# clock.net
KiCad netlist of a schematic drawn in EAGLE
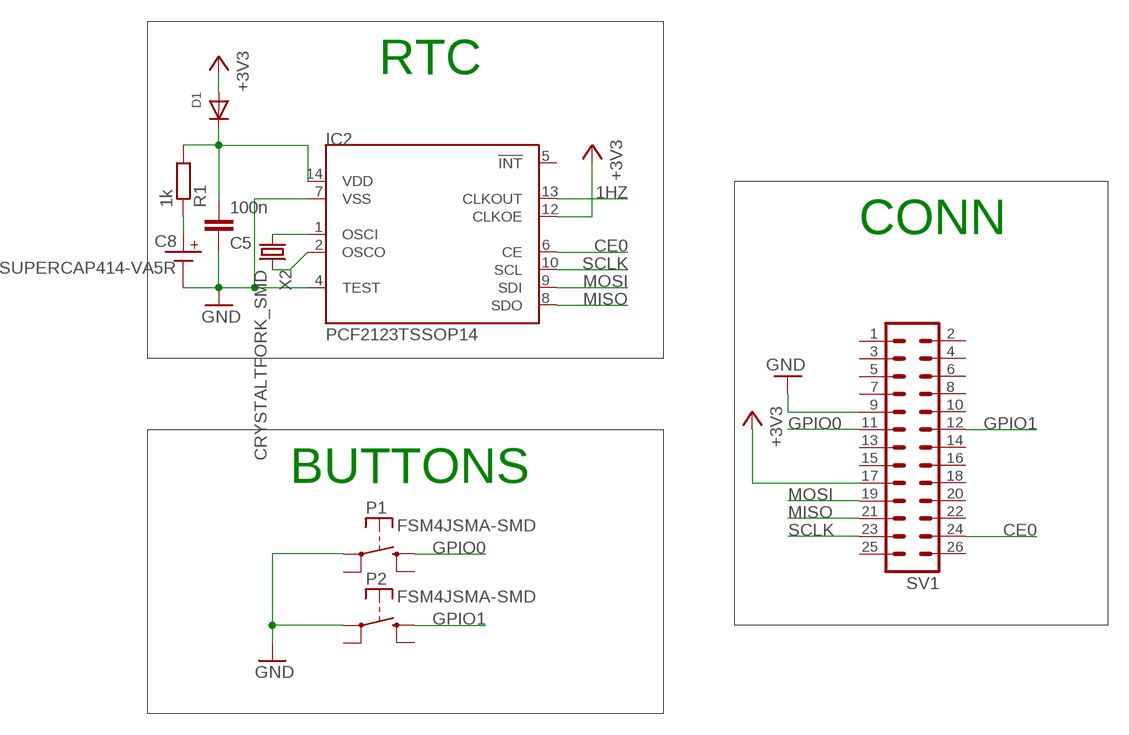
[diagram p0: schematic, sheet 1]

(export (version "E")
  (design (tool "Eeschema 10.0.6"))
  (components
    (comp (ref "C5")
      (value "100n")
      (footprint "eagle-import:C0603K")
      (libsource (lib "eagle-import") (part "C-EUC0603K"))
    )
    (comp (ref "C8")
      (value "SUPERCAP414-VA5R")
      (footprint "eagle-import:414-VA5R")
      (libsource (lib "eagle-import") (part "SUPERCAP414-VA5R"))
    )
    (comp (ref "D1")
      (value "DIODESOD-523")
      (footprint "eagle-import:SOD-523")
      (libsource (lib "eagle-import") (part "DIODESOD-523"))
    )
    (comp (ref "IC2")
      (value "PCF2123TSSOP14")
      (footprint "eagle-import:TSSOP14")
      (libsource (lib "eagle-import") (part "PCF2123TSSOP14"))
    )
    (comp (ref "P1")
      (value "FSM4JSMA-SMD")
      (footprint "eagle-import:FSM4JSMA-SMD")
      (libsource (lib "eagle-import") (part "FSM4JSMA-SMD"))
    )
    (comp (ref "P2")
      (value "FSM4JSMA-SMD")
      (footprint "eagle-import:FSM4JSMA-SMD")
      (libsource (lib "eagle-import") (part "FSM4JSMA-SMD"))
    )
    (comp (ref "R1")
      (value "1k")
      (footprint "eagle-import:R0603")
      (libsource (lib "eagle-import") (part "R-EU_R0603"))
    )
    (comp (ref "SV1")
      (value "MA13-2")
      (footprint "eagle-import:MA13-2")
      (libsource (lib "eagle-import") (part "MA13-2"))
    )
    (comp (ref "X2")
      (value "CRYSTALTFORK_SMD")
      (footprint "eagle-import:TFORK_SMD")
      (libsource (lib "eagle-import") (part "CRYSTALTFORK_SMD"))
    )
  )
  (nets
    (net (code "1") (name "+3V3") (class "Default")
      (node (ref "D1") (pin "A") (pinfunction "A_A") (pintype "passive"))
      (node (ref "IC2") (pin "12") (pinfunction "CLKOE_12") (pintype "input"))
      (node (ref "SV1") (pin "17") (pinfunction "17_17") (pintype "passive"))
    )
    (net (code "2") (name "/1HZ") (class "Default")
      (node (ref "IC2") (pin "13") (pinfunction "CLKOUT_13") (pintype "output"))
    )
    (net (code "3") (name "/CE0") (class "Default")
      (node (ref "IC2") (pin "6") (pinfunction "CE_6") (pintype "input"))
      (node (ref "SV1") (pin "24") (pinfunction "24_24") (pintype "passive"))
    )
    (net (code "4") (name "/GPIO0") (class "Default")
      (node (ref "P1") (pin "P$3") (pinfunction "S_P$3") (pintype "passive"))
      (node (ref "SV1") (pin "11") (pinfunction "11_11") (pintype "passive"))
    )
    (net (code "5") (name "/GPIO1") (class "Default")
      (node (ref "P2") (pin "P$3") (pinfunction "S_P$3") (pintype "passive"))
      (node (ref "SV1") (pin "12") (pinfunction "12_12") (pintype "passive"))
    )
    (net (code "6") (name "/MISO") (class "Default")
      (node (ref "IC2") (pin "8") (pinfunction "SDO_8") (pintype "output"))
      (node (ref "SV1") (pin "21") (pinfunction "21_21") (pintype "passive"))
    )
    (net (code "7") (name "/MOSI") (class "Default")
      (node (ref "IC2") (pin "9") (pinfunction "SDI_9") (pintype "input"))
      (node (ref "SV1") (pin "19") (pinfunction "19_19") (pintype "passive"))
    )
    (net (code "8") (name "/SCLK") (class "Default")
      (node (ref "IC2") (pin "10") (pinfunction "SCL_10") (pintype "input"))
      (node (ref "SV1") (pin "23") (pinfunction "23_23") (pintype "passive"))
    )
    (net (code "9") (name "GND") (class "Default")
      (node (ref "C5") (pin "1") (pinfunction "1_1") (pintype "passive"))
      (node (ref "C8") (pin "MINUS") (pinfunction "MINUS_MINUS") (pintype "passive"))
      (node (ref "IC2") (pin "4") (pinfunction "TEST_4") (pintype "input"))
      (node (ref "IC2") (pin "7") (pinfunction "VSS_7") (pintype "power_in"))
      (node (ref "P1") (pin "P$1") (pinfunction "P_P$1") (pintype "passive"))
      (node (ref "P2") (pin "P$1") (pinfunction "P_P$1") (pintype "passive"))
      (node (ref "SV1") (pin "9") (pinfunction "9_9") (pintype "passive"))
    )
    (net (code "10") (name "Net-(C8-PadPLUS)") (class "Default")
      (node (ref "C8") (pin "PLUS") (pinfunction "PLUS_PLUS") (pintype "passive"))
      (node (ref "R1") (pin "1") (pinfunction "1_1") (pintype "passive"))
    )
    (net (code "11") (name "Net-(D1-C)") (class "Default")
      (node (ref "C5") (pin "2") (pinfunction "2_2") (pintype "passive"))
      (node (ref "D1") (pin "K") (pinfunction "C_K") (pintype "passive"))
      (node (ref "IC2") (pin "14") (pinfunction "VDD_14") (pintype "power_in"))
      (node (ref "R1") (pin "2") (pinfunction "2_2") (pintype "passive"))
    )
    (net (code "12") (name "Net-(IC2-OSCI)") (class "Default")
      (node (ref "IC2") (pin "1") (pinfunction "OSCI_1") (pintype "input"))
      (node (ref "X2") (pin "2") (pinfunction "1_2") (pintype "passive"))
    )
    (net (code "13") (name "Net-(IC2-OSCO)") (class "Default")
      (node (ref "IC2") (pin "2") (pinfunction "OSCO_2") (pintype "input"))
      (node (ref "X2") (pin "3") (pinfunction "2_3") (pintype "passive"))
    )
    (net (code "14") (name "unconnected-(IC2-~{INT}-Pad5)") (class "Default")
      (node (ref "IC2") (pin "5") (pinfunction "~{INT}_5") (pintype "output"))
    )
    (net (code "15") (name "unconnected-(P1-P-PadP$2)") (class "Default")
      (node (ref "P1") (pin "P$2") (pinfunction "P_P$2") (pintype "passive"))
    )
    (net (code "16") (name "unconnected-(P1-S-PadP$4)") (class "Default")
      (node (ref "P1") (pin "P$4") (pinfunction "S_P$4") (pintype "passive"))
    )
    (net (code "17") (name "unconnected-(P2-P-PadP$2)") (class "Default")
      (node (ref "P2") (pin "P$2") (pinfunction "P_P$2") (pintype "passive"))
    )
    (net (code "18") (name "unconnected-(P2-S-PadP$4)") (class "Default")
      (node (ref "P2") (pin "P$4") (pinfunction "S_P$4") (pintype "passive"))
    )
    (net (code "19") (name "unconnected-(SV1-Pad1)") (class "Default")
      (node (ref "SV1") (pin "1") (pinfunction "1_1") (pintype "passive"))
    )
    (net (code "20") (name "unconnected-(SV1-Pad2)") (class "Default")
      (node (ref "SV1") (pin "2") (pinfunction "2_2") (pintype "passive"))
    )
    (net (code "21") (name "unconnected-(SV1-Pad3)") (class "Default")
      (node (ref "SV1") (pin "3") (pinfunction "3_3") (pintype "passive"))
    )
    (net (code "22") (name "unconnected-(SV1-Pad4)") (class "Default")
      (node (ref "SV1") (pin "4") (pinfunction "4_4") (pintype "passive"))
    )
    (net (code "23") (name "unconnected-(SV1-Pad5)") (class "Default")
      (node (ref "SV1") (pin "5") (pinfunction "5_5") (pintype "passive"))
    )
    (net (code "24") (name "unconnected-(SV1-Pad6)") (class "Default")
      (node (ref "SV1") (pin "6") (pinfunction "6_6") (pintype "passive"))
    )
    (net (code "25") (name "unconnected-(SV1-Pad7)") (class "Default")
      (node (ref "SV1") (pin "7") (pinfunction "7_7") (pintype "passive"))
    )
    (net (code "26") (name "unconnected-(SV1-Pad8)") (class "Default")
      (node (ref "SV1") (pin "8") (pinfunction "8_8") (pintype "passive"))
    )
    (net (code "27") (name "unconnected-(SV1-Pad10)") (class "Default")
      (node (ref "SV1") (pin "10") (pinfunction "10_10") (pintype "passive"))
    )
    (net (code "28") (name "unconnected-(SV1-Pad13)") (class "Default")
      (node (ref "SV1") (pin "13") (pinfunction "13_13") (pintype "passive"))
    )
    (net (code "29") (name "unconnected-(SV1-Pad14)") (class "Default")
      (node (ref "SV1") (pin "14") (pinfunction "14_14") (pintype "passive"))
    )
    (net (code "30") (name "unconnected-(SV1-Pad15)") (class "Default")
      (node (ref "SV1") (pin "15") (pinfunction "15_15") (pintype "passive"))
    )
    (net (code "31") (name "unconnected-(SV1-Pad16)") (class "Default")
      (node (ref "SV1") (pin "16") (pinfunction "16_16") (pintype "passive"))
    )
    (net (code "32") (name "unconnected-(SV1-Pad18)") (class "Default")
      (node (ref "SV1") (pin "18") (pinfunction "18_18") (pintype "passive"))
    )
    (net (code "33") (name "unconnected-(SV1-Pad20)") (class "Default")
      (node (ref "SV1") (pin "20") (pinfunction "20_20") (pintype "passive"))
    )
    (net (code "34") (name "unconnected-(SV1-Pad22)") (class "Default")
      (node (ref "SV1") (pin "22") (pinfunction "22_22") (pintype "passive"))
    )
    (net (code "35") (name "unconnected-(SV1-Pad25)") (class "Default")
      (node (ref "SV1") (pin "25") (pinfunction "25_25") (pintype "passive"))
    )
    (net (code "36") (name "unconnected-(SV1-Pad26)") (class "Default")
      (node (ref "SV1") (pin "26") (pinfunction "26_26") (pintype "passive"))
    )
  )
)
